# TPS5430.net
KiCad netlist of a schematic drawn in EAGLE
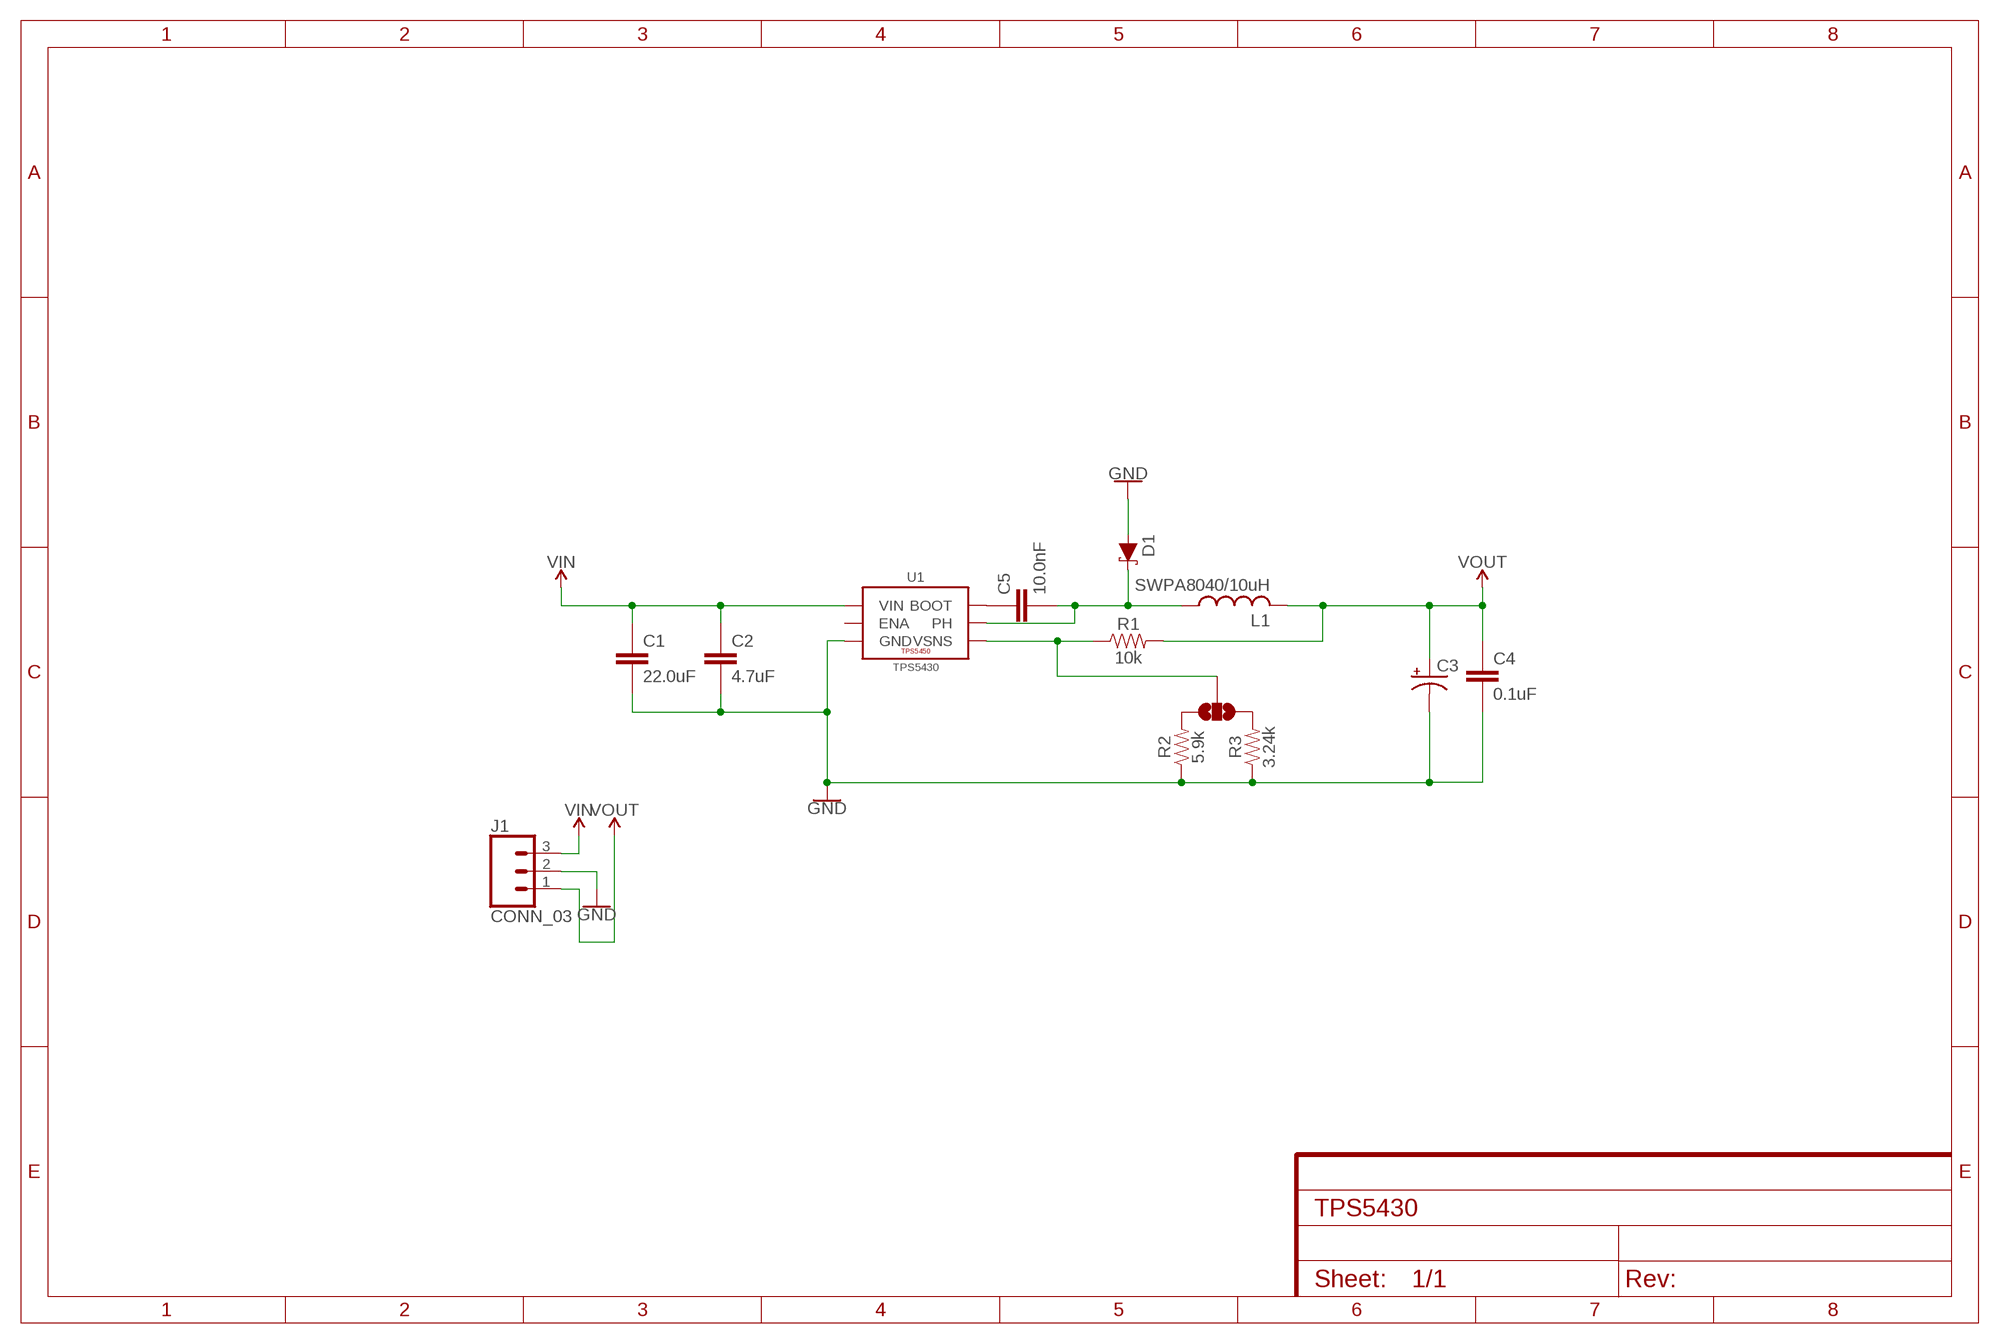
[diagram p0: schematic, sheet 1]

(export (version "E")
  (design (tool "Eeschema 10.0.6"))
  (components
    (comp (ref "C1")
      (value "22.0uF")
      (footprint "eagle-import:C1210")
      (libsource (lib "eagle-import") (part "CAPACITOR1210"))
    )
    (comp (ref "C2")
      (value "4.7uF")
      (footprint "eagle-import:C0603")
      (libsource (lib "eagle-import") (part "CAPACITOR0603"))
    )
    (comp (ref "C3")
      (value "220uF")
      (footprint "eagle-import:D_7343-31R")
      (libsource (lib "eagle-import") (part "CPOL-USD/7343-31R"))
    )
    (comp (ref "C4")
      (value "0.1uF")
      (footprint "eagle-import:C0603")
      (libsource (lib "eagle-import") (part "CAPACITOR0603"))
    )
    (comp (ref "C5")
      (value "10.0nF")
      (footprint "eagle-import:C0603")
      (libsource (lib "eagle-import") (part "CAPACITOR0603"))
    )
    (comp (ref "D1")
      (value "3A/40V/500mV")
      (footprint "eagle-import:SMA-DIODE")
      (libsource (lib "eagle-import") (part "DIODE-SCHOTTKY-B340A"))
    )
    (comp (ref "J1")
      (value "CONN_03")
      (footprint "eagle-import:1X03_LOCK")
      (libsource (lib "eagle-import") (part "CONN_03"))
    )
    (comp (ref "JP1")
      (value "JUMPER-SMT_3_NO_NO-SILK")
      (footprint "eagle-import:SMT-JUMPER_3_NO_NO-SILK")
      (libsource (lib "eagle-import") (part "JUMPER-SMT_3_NO_NO-SILK"))
    )
    (comp (ref "L1")
      (value "SWPA8040/10uH")
      (footprint "eagle-import:SWPA8040")
      (libsource (lib "eagle-import") (part "INDUCTORSWPA8040"))
    )
    (comp (ref "R1")
      (value "10k")
      (footprint "eagle-import:R0603")
      (libsource (lib "eagle-import") (part "RESISTOR0603"))
    )
    (comp (ref "R2")
      (value "5.9k")
      (footprint "eagle-import:R0603")
      (libsource (lib "eagle-import") (part "RESISTOR0603"))
    )
    (comp (ref "R3")
      (value "3.24k")
      (footprint "eagle-import:R0603")
      (libsource (lib "eagle-import") (part "RESISTOR0603"))
    )
    (comp (ref "U1")
      (value "TPS5430")
      (footprint "eagle-import:POWERPAD-SOIC-8")
      (libsource (lib "eagle-import") (part "TPS5450"))
    )
  )
  (nets
    (net (code "1") (name "GND") (class "Default")
      (node (ref "C1") (pin "2") (pinfunction "2_2") (pintype "passive"))
      (node (ref "C2") (pin "2") (pinfunction "2_2") (pintype "passive"))
      (node (ref "C3") (pin "-") (pinfunction "-_-") (pintype "passive"))
      (node (ref "C4") (pin "2") (pinfunction "2_2") (pintype "passive"))
      (node (ref "D1") (pin "A") (pinfunction "A_A") (pintype "passive"))
      (node (ref "J1") (pin "2") (pinfunction "2_2") (pintype "passive"))
      (node (ref "R2") (pin "1") (pinfunction "1_1") (pintype "passive"))
      (node (ref "R3") (pin "1") (pinfunction "1_1") (pintype "passive"))
      (node (ref "U1") (pin "6") (pinfunction "GND_6") (pintype "power_in"))
      (node (ref "U1") (pin "9") (pinfunction "GND_9") (pintype "power_in"))
      (node (ref "U1") (pin "P$1") (pinfunction "GND_P$1") (pintype "power_in"))
      (node (ref "U1") (pin "P$2") (pinfunction "GND_P$2") (pintype "power_in"))
      (node (ref "U1") (pin "P$3") (pinfunction "GND_P$3") (pintype "power_in"))
      (node (ref "U1") (pin "P$4") (pinfunction "GND_P$4") (pintype "power_in"))
      (node (ref "U1") (pin "P$5") (pinfunction "GND_P$5") (pintype "power_in"))
      (node (ref "U1") (pin "P$6") (pinfunction "GND_P$6") (pintype "power_in"))
    )
    (net (code "2") (name "Net-(JP1-Pad1)") (class "Default")
      (node (ref "JP1") (pin "1") (pinfunction "1_1") (pintype "passive"))
      (node (ref "R3") (pin "2") (pinfunction "2_2") (pintype "passive"))
    )
    (net (code "3") (name "Net-(JP1-Pad3)") (class "Default")
      (node (ref "JP1") (pin "3") (pinfunction "3_3") (pintype "passive"))
      (node (ref "R2") (pin "2") (pinfunction "2_2") (pintype "passive"))
    )
    (net (code "4") (name "Net-(L1-1)") (class "Default")
      (node (ref "C5") (pin "2") (pinfunction "2_2") (pintype "passive"))
      (node (ref "D1") (pin "C") (pinfunction "C_C") (pintype "passive"))
      (node (ref "L1") (pin "P1") (pinfunction "1_P1") (pintype "passive"))
      (node (ref "U1") (pin "8") (pinfunction "PH_8") (pintype "bidirectional"))
    )
    (net (code "5") (name "Net-(U1-BOOT)") (class "Default")
      (node (ref "C5") (pin "1") (pinfunction "1_1") (pintype "passive"))
      (node (ref "U1") (pin "1") (pinfunction "BOOT_1") (pintype "bidirectional"))
    )
    (net (code "6") (name "Net-(U1-VSNS)") (class "Default")
      (node (ref "JP1") (pin "2") (pinfunction "2_2") (pintype "passive"))
      (node (ref "R1") (pin "1") (pinfunction "1_1") (pintype "passive"))
      (node (ref "U1") (pin "4") (pinfunction "VSNS_4") (pintype "input"))
    )
    (net (code "7") (name "VIN") (class "Default")
      (node (ref "C1") (pin "1") (pinfunction "1_1") (pintype "passive"))
      (node (ref "C2") (pin "1") (pinfunction "1_1") (pintype "passive"))
      (node (ref "J1") (pin "3") (pinfunction "3_3") (pintype "passive"))
      (node (ref "U1") (pin "7") (pinfunction "VIN_7") (pintype "power_in"))
    )
    (net (code "8") (name "VOUT") (class "Default")
      (node (ref "C3") (pin "+") (pinfunction "+_+") (pintype "passive"))
      (node (ref "C4") (pin "1") (pinfunction "1_1") (pintype "passive"))
      (node (ref "J1") (pin "1") (pinfunction "1_1") (pintype "passive"))
      (node (ref "L1") (pin "P2") (pinfunction "2_P2") (pintype "passive"))
      (node (ref "R1") (pin "2") (pinfunction "2_2") (pintype "passive"))
    )
    (net (code "9") (name "unconnected-(U1-ENA-Pad5)") (class "Default")
      (node (ref "U1") (pin "5") (pinfunction "ENA_5") (pintype "input"))
    )
    (net (code "10") (name "unconnected-(U1-NC-Pad2)") (class "Default")
      (node (ref "U1") (pin "2") (pinfunction "NC_2") (pintype "no_connect"))
    )
    (net (code "11") (name "unconnected-(U1-NC-Pad3)") (class "Default")
      (node (ref "U1") (pin "3") (pinfunction "NC_3") (pintype "no_connect"))
    )
  )
)
